# PD_MK2_Power.net
KiCad netlist of a schematic drawn in Altium Designer
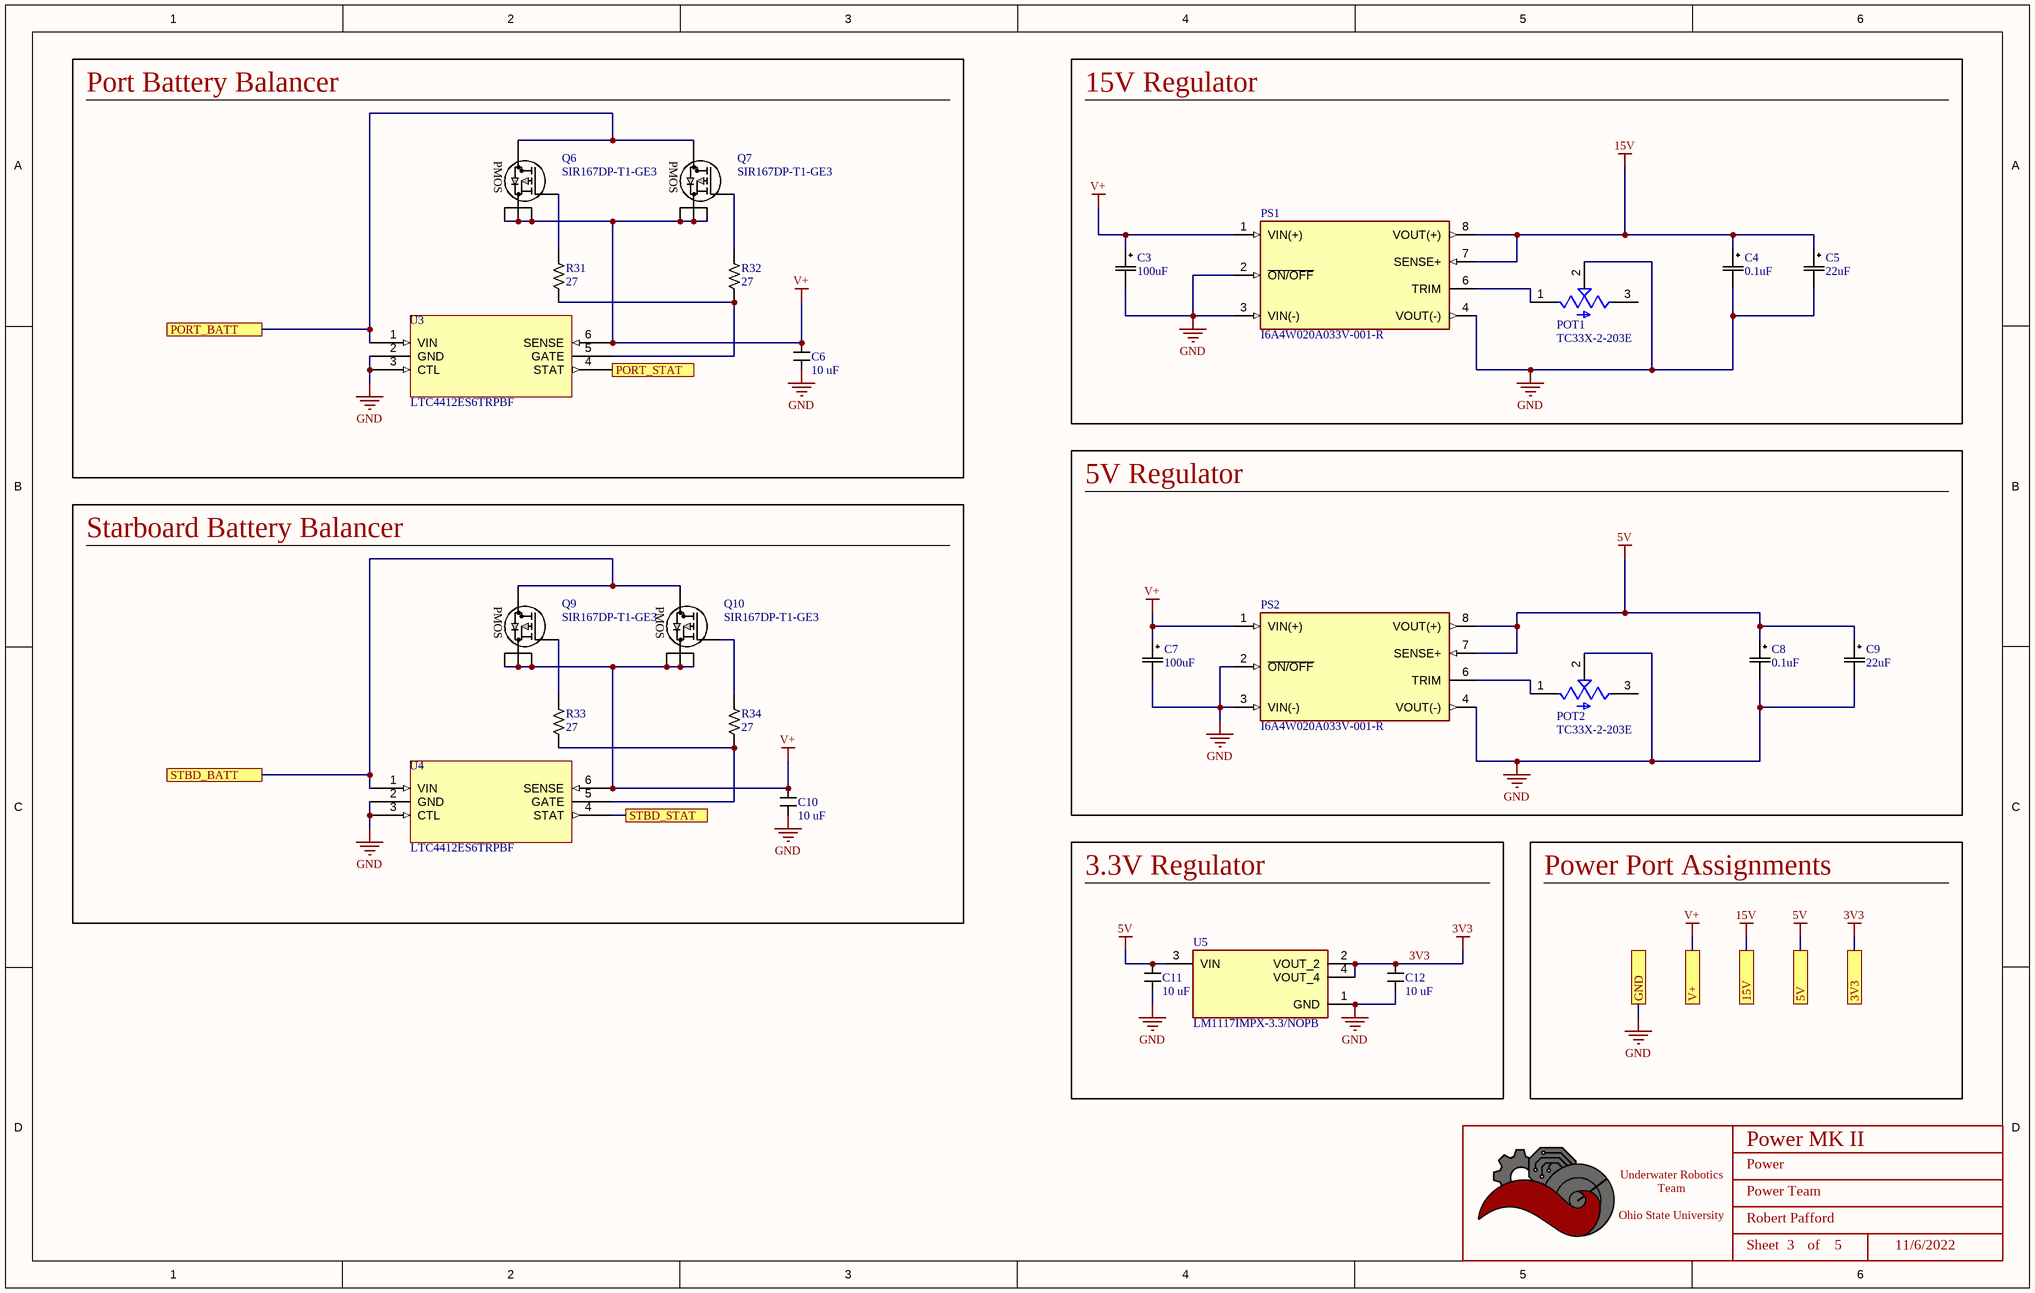
[diagram p0: PD_MK2_Power.SchDoc]

(export (version "E")
  (design (tool "Eeschema 10.0.6"))
  (components
    (comp (ref "C3")
      (value "100uF")
      (footprint "PCAP_8x5.4-ELECT_NCA")
      (description "100 µF 35 V Aluminum Electrolytic Capacitors Radial, Can - SMD 1000 Hrs")
      (fields
        (field (name "MANUFACTURER_PART_NUMBER") "UCB1V0R1MCL1GS")
        (field (name "Comment") "100uF electrolytic 35 V")
        (field (name "COPYRIGHT") "Copyright (C) 2022 Ultra Librarian. All rights reserved.")
        (field (name "MADE BY") "Tyson Nguyen")
      )
      (libsource (lib "Capacitors") (part "CAP ALUM 100UF 20% 35V SMD"))
    )
    (comp (ref "C4")
      (value "0.1uF")
      (footprint "U2-D_NCH")
      (description "0.1 µF 35 V Aluminum Electrolytic Capacitors Radial, Can - SMD 7000 Hrs @ 105°C")
      (fields
        (field (name "MANUFACTURER_PART_NUMBER") "UCB1V0R1MCL1GS")
        (field (name "Comment") "0.1uF electrolytic 35 V")
        (field (name "COPYRIGHT") "Copyright (C) 2022 Ultra Librarian. All rights reserved.")
        (field (name "MADE BY") "Tyson Nguyen")
      )
      (libsource (lib "Capacitors") (part "CAP ALUM 0.1UF 20% 35V SMD"))
    )
    (comp (ref "C5")
      (value "22uF")
      (footprint "PCAP_8x5.4-ELECT_NCA")
      (description "22 µF 35 V Aluminum Electrolytic Capacitors Radial, Can - SMD 1000 Hrs")
      (fields
        (field (name "VOLTAGE") "35V")
        (field (name "Comment") "22uF electrolytic 35 V")
        (field (name "MADE BY") "Robert Pafford")
      )
      (libsource (lib "Capacitors") (part "CAP ALUM 22UF 20% 35V SMD"))
    )
    (comp (ref "C6")
      (value "10uF Ceramic 25V")
      (footprint "CAPACITOR_1206")
      (description "Cap 10uF 25V +/-10%\r\nCeramic 1206")
      (fields
        (field (name "TOLERANCE") "+/- 10%")
        (field (name "VOLTAGE") "25V")
        (field (name "VALUE (UF)") "10 uF")
        (field (name "MADE BY") "Robert Pafford")
      )
      (libsource (lib "Capacitors") (part "CAPACITOR_10uF_1206"))
    )
    (comp (ref "C7")
      (value "100uF")
      (footprint "PCAP_8x5.4-ELECT_NCA")
      (description "100 µF 35 V Aluminum Electrolytic Capacitors Radial, Can - SMD 1000 Hrs")
      (fields
        (field (name "MANUFACTURER_PART_NUMBER") "UCB1V0R1MCL1GS")
        (field (name "Comment") "100uF electrolytic 35 V")
        (field (name "COPYRIGHT") "Copyright (C) 2022 Ultra Librarian. All rights reserved.")
        (field (name "MADE BY") "Tyson Nguyen")
      )
      (libsource (lib "Capacitors") (part "CAP ALUM 100UF 20% 35V SMD"))
    )
    (comp (ref "C8")
      (value "0.1uF")
      (footprint "U2-D_NCH")
      (description "0.1 µF 35 V Aluminum Electrolytic Capacitors Radial, Can - SMD 7000 Hrs @ 105°C")
      (fields
        (field (name "MANUFACTURER_PART_NUMBER") "UCB1V0R1MCL1GS")
        (field (name "Comment") "0.1uF electrolytic 35 V")
        (field (name "COPYRIGHT") "Copyright (C) 2022 Ultra Librarian. All rights reserved.")
        (field (name "MADE BY") "Tyson Nguyen")
      )
      (libsource (lib "Capacitors") (part "CAP ALUM 0.1UF 20% 35V SMD"))
    )
    (comp (ref "C9")
      (value "22uF")
      (footprint "PCAP_8x5.4-ELECT_NCA")
      (description "22 µF 35 V Aluminum Electrolytic Capacitors Radial, Can - SMD 1000 Hrs")
      (fields
        (field (name "VOLTAGE") "35V")
        (field (name "Comment") "22uF electrolytic 35 V")
        (field (name "MADE BY") "Robert Pafford")
      )
      (libsource (lib "Capacitors") (part "CAP ALUM 22UF 20% 35V SMD"))
    )
    (comp (ref "C10")
      (value "10uF Ceramic 25V")
      (footprint "CAPACITOR_1206")
      (description "Cap 10uF 25V +/-10%\r\nCeramic 1206")
      (fields
        (field (name "TOLERANCE") "+/- 10%")
        (field (name "VOLTAGE") "25V")
        (field (name "VALUE (UF)") "10 uF")
        (field (name "MADE BY") "Robert Pafford")
      )
      (libsource (lib "Capacitors") (part "CAPACITOR_10uF_1206"))
    )
    (comp (ref "C11")
      (value "10uF Ceramic 6.3V")
      (footprint "CAPACITOR_0603")
      (description "Cap 10uF 6.3V +/-20%\r\nCeramic 0603")
      (fields
        (field (name "TOLERANCE") "+/- 20%")
        (field (name "VOLTAGE") "6.3V")
        (field (name "VALUE (UF)") "10 uF")
        (field (name "MADE BY") "Flip B")
      )
      (libsource (lib "Capacitors") (part "CAPACITOR_10uF_0603"))
    )
    (comp (ref "C12")
      (value "10uF Ceramic 6.3V")
      (footprint "CAPACITOR_0603")
      (description "Cap 10uF 6.3V +/-20%\r\nCeramic 0603")
      (fields
        (field (name "TOLERANCE") "+/- 20%")
        (field (name "VOLTAGE") "6.3V")
        (field (name "VALUE (UF)") "10 uF")
        (field (name "MADE BY") "Flip B")
      )
      (libsource (lib "Capacitors") (part "CAPACITOR_10uF_0603"))
    )
    (comp (ref "POT1")
      (value "TC33X-2-203E")
      (footprint "TRIM_TC33X-2-203E")
      (description "20 kOhms 0.1W, 1/10W J Lead Surface Mount Trimmer Potentiometer Cermet 1 Turn Top Adjustment")
      (fields (field (name "MF") "Bourns") (field (name "DIGI-KEY_PART_NUMBER") "TC33X-2-203ECT-ND"))
      (libsource (lib "TC33X-2-203E") (part "TC33X-2-203E"))
    )
    (comp (ref "POT2")
      (value "TC33X-2-203E")
      (footprint "TRIM_TC33X-2-203E")
      (description "20 kOhms 0.1W, 1/10W J Lead Surface Mount Trimmer Potentiometer Cermet 1 Turn Top Adjustment")
      (fields (field (name "MF") "Bourns") (field (name "DIGI-KEY_PART_NUMBER") "TC33X-2-203ECT-ND"))
      (libsource (lib "TC33X-2-203E") (part "TC33X-2-203E"))
    )
    (comp (ref "PS1")
      (value "I6A4W020A033V-001-R")
      (footprint "CONV_I6A4W020A033V-001-R")
      (description "Non-Isolated PoL Module DC DC Converter 1 Output 3.3 ~ 15V 20A 9V - 53V Input")
      (fields (field (name "MF") "TDK-Lambda Americas"))
      (libsource (lib "I6A4W020A033V-001-R") (part "I6A4W020A033V-001-R"))
    )
    (comp (ref "PS2")
      (value "I6A4W020A033V-001-R")
      (footprint "CONV_I6A4W020A033V-001-R")
      (description "Non-Isolated PoL Module DC DC Converter 1 Output 3.3 ~ 15V 20A 9V - 53V Input")
      (fields (field (name "MF") "TDK-Lambda Americas"))
      (libsource (lib "I6A4W020A033V-001-R") (part "I6A4W020A033V-001-R"))
    )
    (comp (ref "Q6")
      (value "SIR167DP-T1-GE3")
      (footprint "MOSFET_7DP-T1-GE3_VIS")
      (description "P-Channel 30 V 60A (Tc) 65.8W (Tc) Surface Mount PowerPAK® SO-8")
      (fields (field (name "COPYRIGHT") "Copyright (C) 2022 Ultra Librarian. All rights reserved."))
      (libsource (lib "Transistors") (part "SIR167DP-T1-GE3"))
    )
    (comp (ref "Q7")
      (value "SIR167DP-T1-GE3")
      (footprint "MOSFET_7DP-T1-GE3_VIS")
      (description "P-Channel 30 V 60A (Tc) 65.8W (Tc) Surface Mount PowerPAK® SO-8")
      (fields (field (name "COPYRIGHT") "Copyright (C) 2022 Ultra Librarian. All rights reserved."))
      (libsource (lib "Transistors") (part "SIR167DP-T1-GE3"))
    )
    (comp (ref "Q9")
      (value "SIR167DP-T1-GE3")
      (footprint "MOSFET_7DP-T1-GE3_VIS")
      (description "P-Channel 30 V 60A (Tc) 65.8W (Tc) Surface Mount PowerPAK® SO-8")
      (fields (field (name "COPYRIGHT") "Copyright (C) 2022 Ultra Librarian. All rights reserved."))
      (libsource (lib "Transistors") (part "SIR167DP-T1-GE3"))
    )
    (comp (ref "Q10")
      (value "SIR167DP-T1-GE3")
      (footprint "MOSFET_7DP-T1-GE3_VIS")
      (description "P-Channel 30 V 60A (Tc) 65.8W (Tc) Surface Mount PowerPAK® SO-8")
      (fields (field (name "COPYRIGHT") "Copyright (C) 2022 Ultra Librarian. All rights reserved."))
      (libsource (lib "Transistors") (part "SIR167DP-T1-GE3"))
    )
    (comp (ref "R31")
      (value "27 Ohm 5% 1/8W")
      (footprint "RESISTOR_0603")
      (description "RES 27 OHM 5% 1/8W 0603")
      (fields
        (field (name "TOLERANCE") "+/- 5%")
        (field (name "VALUE  (OHMS)") "27")
        (field (name "MADE BY") "Robert Pafford")
      )
      (libsource (lib "Resistors") (part "RESISTOR_27_0603"))
    )
    (comp (ref "R32")
      (value "27 Ohm 5% 1/8W")
      (footprint "RESISTOR_0603")
      (description "RES 27 OHM 5% 1/8W 0603")
      (fields
        (field (name "TOLERANCE") "+/- 5%")
        (field (name "VALUE  (OHMS)") "27")
        (field (name "MADE BY") "Robert Pafford")
      )
      (libsource (lib "Resistors") (part "RESISTOR_27_0603"))
    )
    (comp (ref "R33")
      (value "27 Ohm 5% 1/8W")
      (footprint "RESISTOR_0603")
      (description "RES 27 OHM 5% 1/8W 0603")
      (fields
        (field (name "TOLERANCE") "+/- 5%")
        (field (name "VALUE  (OHMS)") "27")
        (field (name "MADE BY") "Robert Pafford")
      )
      (libsource (lib "Resistors") (part "RESISTOR_27_0603"))
    )
    (comp (ref "R34")
      (value "27 Ohm 5% 1/8W")
      (footprint "RESISTOR_0603")
      (description "RES 27 OHM 5% 1/8W 0603")
      (fields
        (field (name "TOLERANCE") "+/- 5%")
        (field (name "VALUE  (OHMS)") "27")
        (field (name "MADE BY") "Robert Pafford")
      )
      (libsource (lib "Resistors") (part "RESISTOR_27_0603"))
    )
    (comp (ref "U3")
      (value "LTC4412ES6TRPBF")
      (footprint "TSOT-23_S6")
      (description "OR Controller Source Selector Switch P-Channel 2:1 TSOT-23-6")
      (fields (field (name "MP") "LTC4412ES6#TRPBF") (field (name "MF") "Analog Devices"))
      (libsource (lib "Integrated Circuits") (part "LTC4412ES6TRPBF"))
    )
    (comp (ref "U4")
      (value "LTC4412ES6TRPBF")
      (footprint "TSOT-23_S6")
      (description "OR Controller Source Selector Switch P-Channel 2:1 TSOT-23-6")
      (fields (field (name "MP") "LTC4412ES6#TRPBF") (field (name "MF") "Analog Devices"))
      (libsource (lib "Integrated Circuits") (part "LTC4412ES6TRPBF"))
    )
    (comp (ref "U5")
      (value "LM1117IMPX-3.3/NOPB")
      (footprint "SOT-223-4")
      (description "800-mA 15-V linear voltage regulator 4-SOT-223 -40 to 125")
      (fields (field (name "MF") "Texas Instruments"))
      (libsource (lib "Integrated Circuits") (part "LM1117IMPX-3.3/NOPB"))
    )
  )
  (nets
    (net (code "1") (name "/PORT_BATT") (class "Default")
      (node (ref "Q6") (pin "D") (pinfunction "D_D") (pintype "passive"))
      (node (ref "Q7") (pin "D") (pinfunction "D_D") (pintype "passive"))
      (node (ref "U3") (pin "1") (pinfunction "VIN_1") (pintype "input"))
    )
    (net (code "2") (name "/PORT_STAT") (class "Default")
      (node (ref "U3") (pin "4") (pinfunction "STAT_4") (pintype "output"))
    )
    (net (code "3") (name "/STBD_BATT") (class "Default")
      (node (ref "Q10") (pin "D") (pinfunction "D_D") (pintype "passive"))
      (node (ref "Q9") (pin "D") (pinfunction "D_D") (pintype "passive"))
      (node (ref "U4") (pin "1") (pinfunction "VIN_1") (pintype "input"))
    )
    (net (code "4") (name "/STBD_STAT") (class "Default")
      (node (ref "U4") (pin "4") (pinfunction "STAT_4") (pintype "output"))
    )
    (net (code "5") (name "3V3") (class "Default")
      (node (ref "C12") (pin "1") (pinfunction "1_1") (pintype "passive"))
      (node (ref "U5") (pin "2") (pinfunction "VOUT_2_2") (pintype "power_in"))
      (node (ref "U5") (pin "4") (pinfunction "VOUT_4_4") (pintype "power_in"))
    )
    (net (code "6") (name "5V") (class "Default")
      (node (ref "C11") (pin "1") (pinfunction "1_1") (pintype "passive"))
      (node (ref "C8") (pin "1") (pinfunction "1_1") (pintype "passive"))
      (node (ref "C9") (pin "1") (pinfunction "1_1") (pintype "passive"))
      (node (ref "PS2") (pin "7") (pinfunction "SENSE+_7") (pintype "input"))
      (node (ref "PS2") (pin "8") (pinfunction "VOUT(+)_8") (pintype "output"))
      (node (ref "U5") (pin "3") (pinfunction "VIN_3") (pintype "power_in"))
    )
    (net (code "7") (name "15V") (class "Default")
      (node (ref "C4") (pin "1") (pinfunction "1_1") (pintype "passive"))
      (node (ref "C5") (pin "1") (pinfunction "1_1") (pintype "passive"))
      (node (ref "PS1") (pin "7") (pinfunction "SENSE+_7") (pintype "input"))
      (node (ref "PS1") (pin "8") (pinfunction "VOUT(+)_8") (pintype "output"))
    )
    (net (code "8") (name "GND") (class "Default")
      (node (ref "C10") (pin "2") (pinfunction "2_2") (pintype "passive"))
      (node (ref "C11") (pin "2") (pinfunction "2_2") (pintype "passive"))
      (node (ref "C12") (pin "2") (pinfunction "2_2") (pintype "passive"))
      (node (ref "C3") (pin "2") (pinfunction "2_2") (pintype "passive"))
      (node (ref "C4") (pin "2") (pinfunction "2_2") (pintype "passive"))
      (node (ref "C5") (pin "2") (pinfunction "2_2") (pintype "passive"))
      (node (ref "C6") (pin "2") (pinfunction "2_2") (pintype "passive"))
      (node (ref "C7") (pin "2") (pinfunction "2_2") (pintype "passive"))
      (node (ref "C8") (pin "2") (pinfunction "2_2") (pintype "passive"))
      (node (ref "C9") (pin "2") (pinfunction "2_2") (pintype "passive"))
      (node (ref "POT1") (pin "2") (pinfunction "W_2") (pintype "passive"))
      (node (ref "POT2") (pin "2") (pinfunction "W_2") (pintype "passive"))
      (node (ref "PS1") (pin "2") (pinfunction "~{ON/OFF}_2") (pintype "input"))
      (node (ref "PS1") (pin "3") (pinfunction "VIN(-)_3") (pintype "input"))
      (node (ref "PS1") (pin "4") (pinfunction "VOUT(-)_4") (pintype "output"))
      (node (ref "PS2") (pin "2") (pinfunction "~{ON/OFF}_2") (pintype "input"))
      (node (ref "PS2") (pin "3") (pinfunction "VIN(-)_3") (pintype "input"))
      (node (ref "PS2") (pin "4") (pinfunction "VOUT(-)_4") (pintype "output"))
      (node (ref "U3") (pin "2") (pinfunction "GND_2") (pintype "power_in"))
      (node (ref "U3") (pin "3") (pinfunction "CTL_3") (pintype "input"))
      (node (ref "U4") (pin "2") (pinfunction "GND_2") (pintype "power_in"))
      (node (ref "U4") (pin "3") (pinfunction "CTL_3") (pintype "input"))
      (node (ref "U5") (pin "1") (pinfunction "GND_1") (pintype "power_in"))
    )
    (net (code "9") (name "Net-(POT1-CCW)") (class "Default")
      (node (ref "POT1") (pin "1") (pinfunction "CCW_1") (pintype "passive"))
      (node (ref "PS1") (pin "6") (pinfunction "TRIM_6") (pintype "passive"))
    )
    (net (code "10") (name "Net-(POT2-CCW)") (class "Default")
      (node (ref "POT2") (pin "1") (pinfunction "CCW_1") (pintype "passive"))
      (node (ref "PS2") (pin "6") (pinfunction "TRIM_6") (pintype "passive"))
    )
    (net (code "11") (name "Net-(Q6-G)") (class "Default")
      (node (ref "Q6") (pin "4") (pinfunction "G_4") (pintype "passive"))
      (node (ref "R31") (pin "1") (pinfunction "1_1") (pintype "passive"))
    )
    (net (code "12") (name "Net-(Q7-G)") (class "Default")
      (node (ref "Q7") (pin "4") (pinfunction "G_4") (pintype "passive"))
      (node (ref "R32") (pin "1") (pinfunction "1_1") (pintype "passive"))
    )
    (net (code "13") (name "Net-(Q9-G)") (class "Default")
      (node (ref "Q9") (pin "4") (pinfunction "G_4") (pintype "passive"))
      (node (ref "R33") (pin "1") (pinfunction "1_1") (pintype "passive"))
    )
    (net (code "14") (name "Net-(Q10-G)") (class "Default")
      (node (ref "Q10") (pin "4") (pinfunction "G_4") (pintype "passive"))
      (node (ref "R34") (pin "1") (pinfunction "1_1") (pintype "passive"))
    )
    (net (code "15") (name "Net-(U3-GATE)") (class "Default")
      (node (ref "R31") (pin "2") (pinfunction "2_2") (pintype "passive"))
      (node (ref "R32") (pin "2") (pinfunction "2_2") (pintype "passive"))
      (node (ref "U3") (pin "5") (pinfunction "GATE_5") (pintype "passive"))
    )
    (net (code "16") (name "Net-(U4-GATE)") (class "Default")
      (node (ref "R33") (pin "2") (pinfunction "2_2") (pintype "passive"))
      (node (ref "R34") (pin "2") (pinfunction "2_2") (pintype "passive"))
      (node (ref "U4") (pin "5") (pinfunction "GATE_5") (pintype "passive"))
    )
    (net (code "17") (name "V+") (class "Default")
      (node (ref "C10") (pin "1") (pinfunction "1_1") (pintype "passive"))
      (node (ref "C3") (pin "1") (pinfunction "1_1") (pintype "passive"))
      (node (ref "C6") (pin "1") (pinfunction "1_1") (pintype "passive"))
      (node (ref "C7") (pin "1") (pinfunction "1_1") (pintype "passive"))
      (node (ref "PS1") (pin "1") (pinfunction "VIN(+)_1") (pintype "input"))
      (node (ref "PS2") (pin "1") (pinfunction "VIN(+)_1") (pintype "input"))
      (node (ref "Q10") (pin "1") (pinfunction "S_1") (pintype "passive"))
      (node (ref "Q10") (pin "2") (pinfunction "S_2") (pintype "passive"))
      (node (ref "Q10") (pin "3") (pinfunction "S_3") (pintype "passive"))
      (node (ref "Q6") (pin "1") (pinfunction "S_1") (pintype "passive"))
      (node (ref "Q6") (pin "2") (pinfunction "S_2") (pintype "passive"))
      (node (ref "Q6") (pin "3") (pinfunction "S_3") (pintype "passive"))
      (node (ref "Q7") (pin "1") (pinfunction "S_1") (pintype "passive"))
      (node (ref "Q7") (pin "2") (pinfunction "S_2") (pintype "passive"))
      (node (ref "Q7") (pin "3") (pinfunction "S_3") (pintype "passive"))
      (node (ref "Q9") (pin "1") (pinfunction "S_1") (pintype "passive"))
      (node (ref "Q9") (pin "2") (pinfunction "S_2") (pintype "passive"))
      (node (ref "Q9") (pin "3") (pinfunction "S_3") (pintype "passive"))
      (node (ref "U3") (pin "6") (pinfunction "SENSE_6") (pintype "input"))
      (node (ref "U4") (pin "6") (pinfunction "SENSE_6") (pintype "input"))
    )
    (net (code "18") (name "unconnected-(POT1-CW-Pad3)") (class "Default")
      (node (ref "POT1") (pin "3") (pinfunction "CW_3") (pintype "passive"))
    )
    (net (code "19") (name "unconnected-(POT2-CW-Pad3)") (class "Default")
      (node (ref "POT2") (pin "3") (pinfunction "CW_3") (pintype "passive"))
    )
  )
)
